# Controller_Sheet.net
KiCad netlist of a schematic drawn in Altium Designer
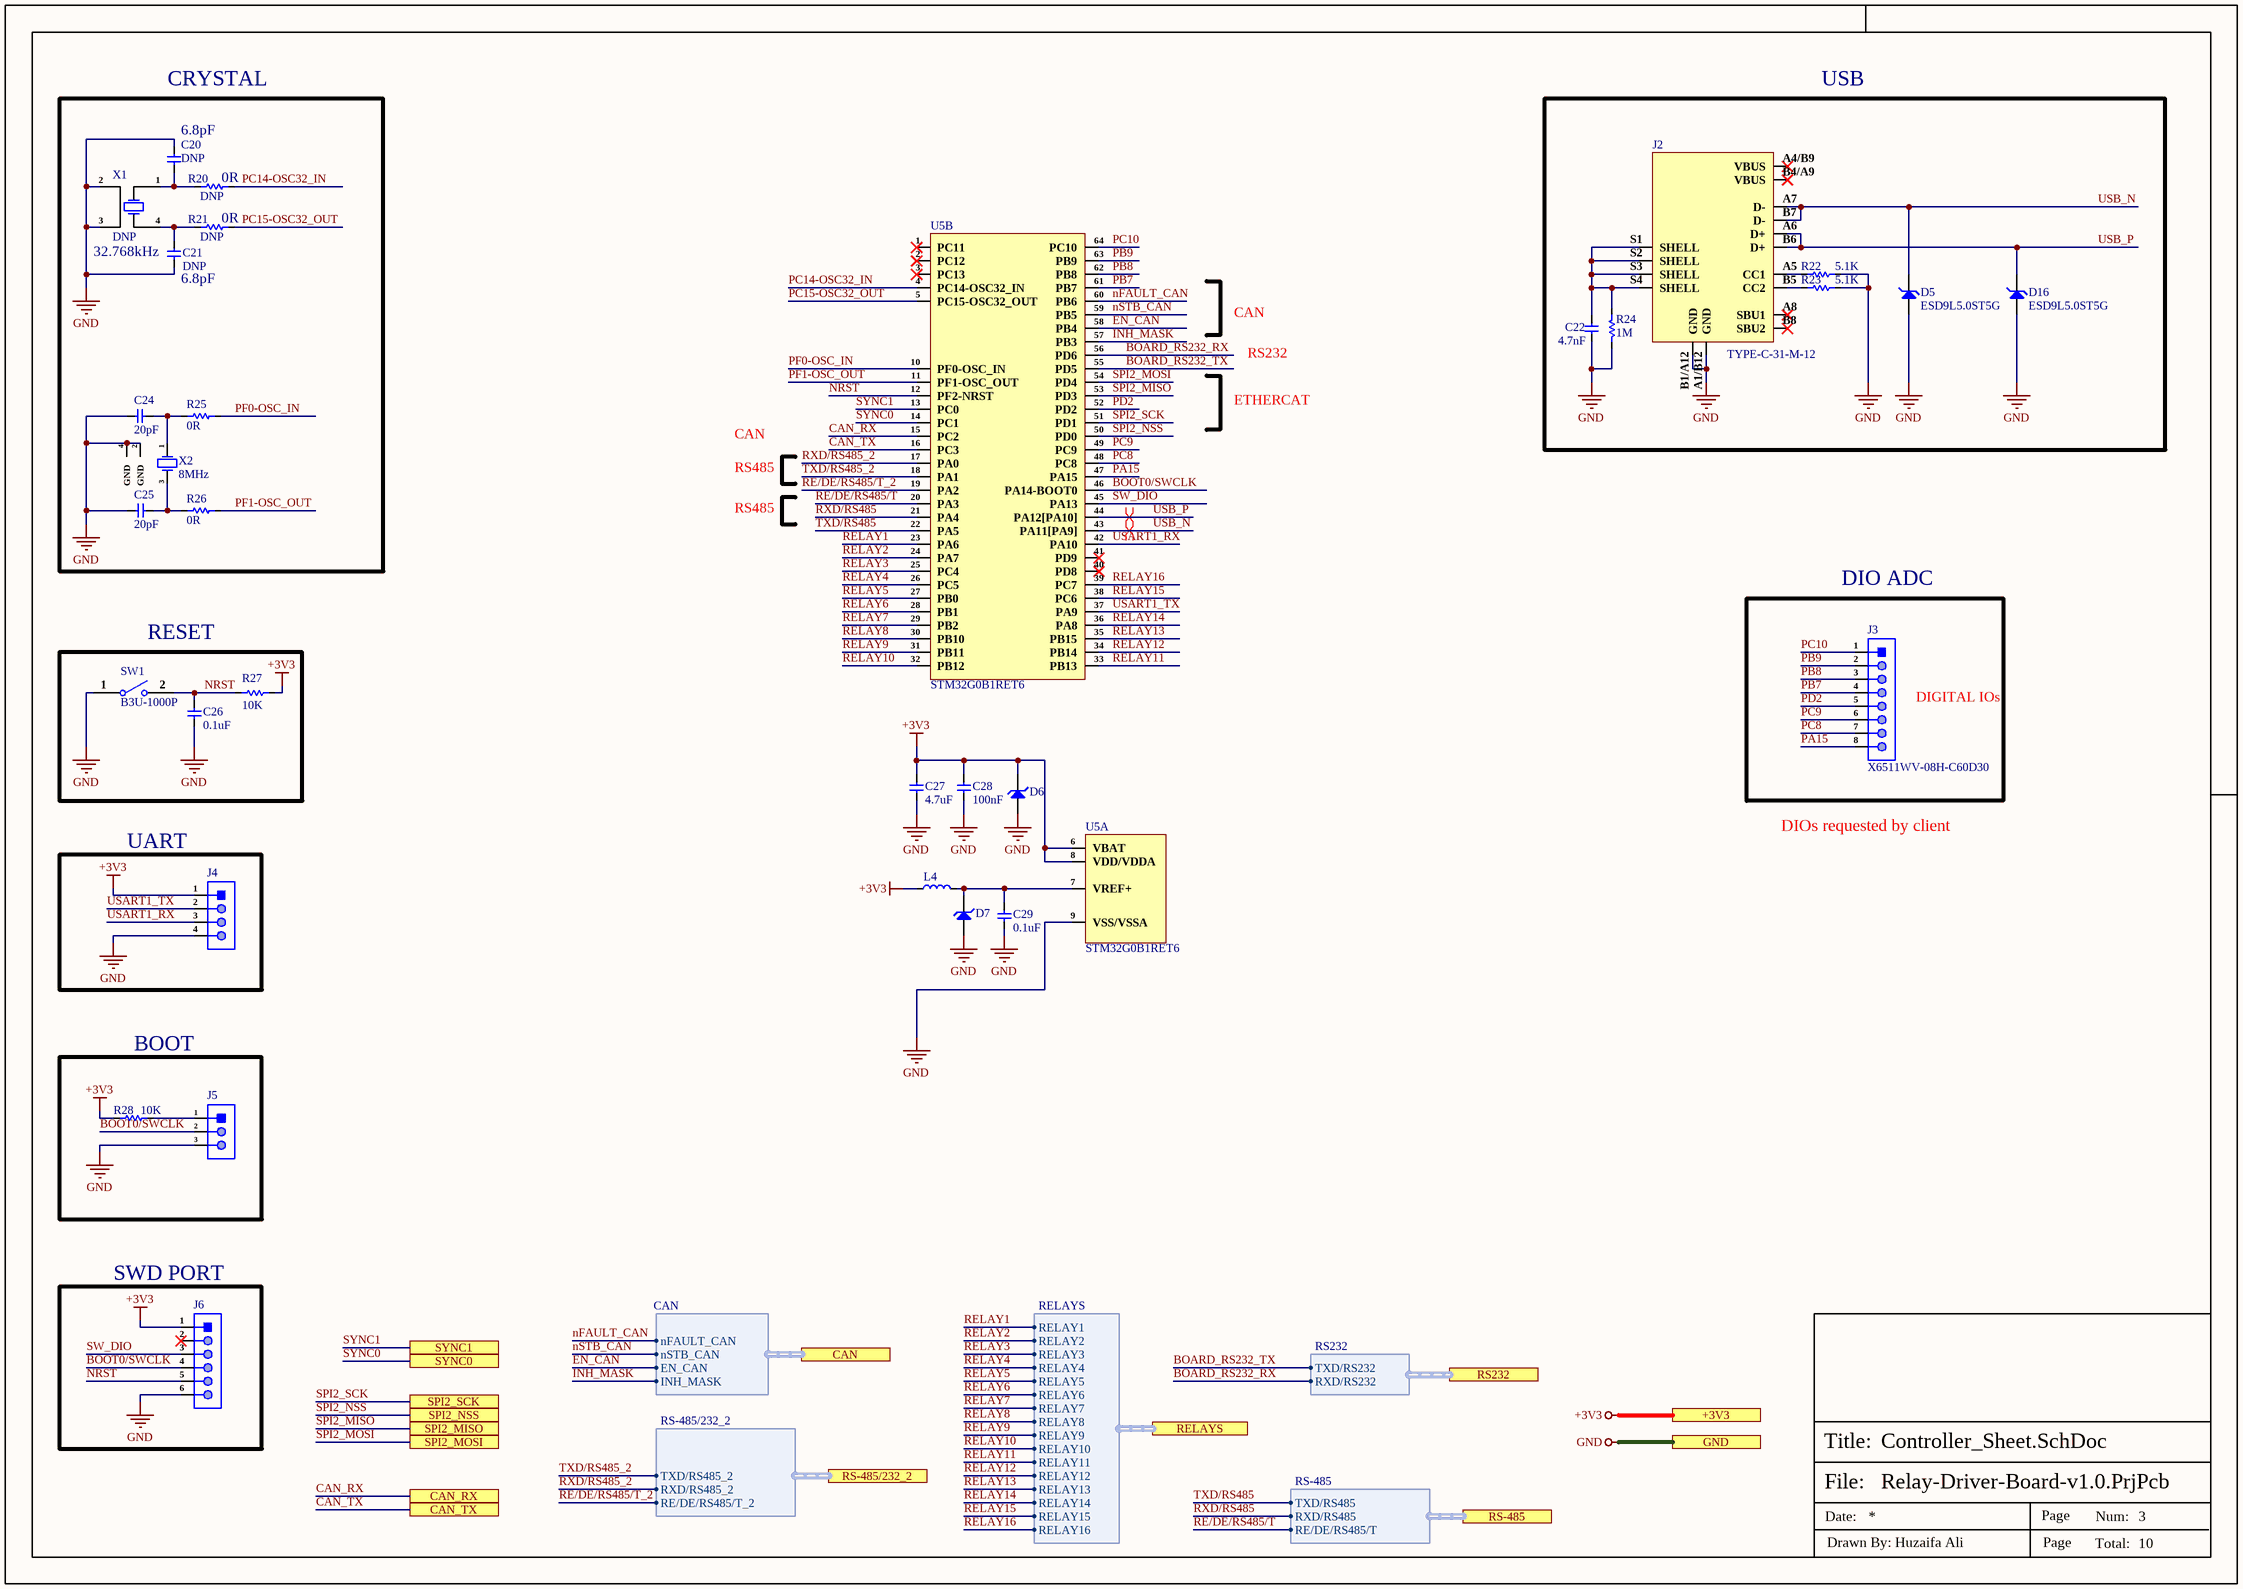
[diagram p0: Controller_Sheet.SchDoc]

(export (version "E")
  (design (tool "Eeschema 10.0.6"))
  (components
    (comp (ref "C20")
      (value "DNP")
      (footprint "Cap-0402")
      (description "CAP CER 6.8PF 50V C0G/NPO 0402")
      (fields
        (field (name "MANUFACTURER") "Yageo")
        (field (name "MANUFACTURER PART NUMBER") "CC0402CRNPO9BN6R8")
      )
      (libsource (lib "eSpark Libraries") (part "CC0402CRNPO9BN6R8"))
    )
    (comp (ref "C21")
      (value "DNP")
      (footprint "Cap-0402")
      (description "CAP CER 6.8PF 50V C0G/NPO 0402")
      (fields
        (field (name "MANUFACTURER") "Yageo")
        (field (name "MANUFACTURER PART NUMBER") "CC0402CRNPO9BN6R8")
      )
      (libsource (lib "eSpark Libraries") (part "CC0402CRNPO9BN6R8"))
    )
    (comp (ref "C22")
      (value "4.7nF")
      (footprint "Cap-0603")
      (description "CAP CER 4700PF 50V C0G/NPO 0603")
      (fields
        (field (name "MANUFACTURER") "Yageo")
        (field (name "MANUFACTURER PART NUMBER") "CC0603JRNPO9BN472")
      )
      (libsource (lib "eSpark_centralized_Library(2022)") (part "CC0603JRNPO9BN472"))
    )
    (comp (ref "C24")
      (value "20pF")
      (footprint "Cap-0402")
      (description "CAP CER 20PF 50V C0G/NPO 0402")
      (fields (field (name "LCSC PART NUMBER") "C107000") (field (name "MANUFACTURER") "Yageo"))
      (libsource (lib "eSpark Libraries") (part "CC0402JRNPO9BN200"))
    )
    (comp (ref "C25")
      (value "20pF")
      (footprint "Cap-0402")
      (description "CAP CER 20PF 50V C0G/NPO 0402")
      (fields (field (name "LCSC PART NUMBER") "C107000") (field (name "MANUFACTURER") "Yageo"))
      (libsource (lib "eSpark Libraries") (part "CC0402JRNPO9BN200"))
    )
    (comp (ref "C26")
      (value "0.1uF")
      (footprint "Cap-0402")
      (description "CAP CER 0.1UF 16V X7R 0402")
      (fields
        (field (name "MANUFACTURER") "Yageo")
        (field (name "MANUFACTURER PART NUMBER") "CC0402JRX7R7BB104")
      )
      (libsource (lib "eSpark Libraries") (part "CC0402JRX7R7BB104"))
    )
    (comp (ref "C27")
      (value "4.7uF")
      (footprint "Cap-0402")
      (description "CAP CER 4.7UF 10V X5R 0402")
      (fields
        (field (name "MANUFACTURER") "Yageo")
        (field (name "MANUFACTURER PART NUMBER") "CC0402KRX5R6BB475")
      )
      (libsource (lib "eSpark Libraries") (part "CC0402KRX5R6BB475"))
    )
    (comp (ref "C28")
      (value "100nF")
      (footprint "cap-0402")
      (description "CAP CER 0.1UF 50V X7R 0402")
      (fields
        (field (name "MANUFACTURER") "TDK")
        (field (name "MANUFACTURER PART NUMBER") "C1005X7R1H104KT000F")
      )
      (libsource (lib "eSpark Libraries") (part "C1005X7R1H104KT000F"))
    )
    (comp (ref "C29")
      (value "0.1uF")
      (footprint "Cap-0402")
      (description "CAP CER 0.1UF 16V X7R 0402")
      (fields
        (field (name "MANUFACTURER") "Yageo")
        (field (name "MANUFACTURER PART NUMBER") "CC0402JRX7R7BB104")
      )
      (libsource (lib "eSpark Libraries") (part "CC0402JRX7R7BB104"))
    )
    (comp (ref "D5")
      (value "ESD9L5.0ST5G")
      (footprint "SOD-923.")
      (description "TVS DIODE 5V 9.8V SOD923")
      (fields (field (name "MANUFACTURER") "ON Semiconductor") (field (name "LCSC PART NUMBER") "C82326"))
      (libsource (lib "eSpark Libraries") (part "ESD9L5.0ST5G"))
    )
    (comp (ref "D6")
      (value "AZ3003-01G")
      (footprint "SOD-123")
      (description "TVS SURGE PROTECTOR 1-CH 3.3V")
      (fields (field (name "MANUFACTURER") "Amazing"))
      (libsource (lib "eSpark Libraries") (part "AZ3003-01G"))
    )
    (comp (ref "D7")
      (value "AZ3003-01G")
      (footprint "SOD-123")
      (description "TVS SURGE PROTECTOR 1-CH 3.3V")
      (fields (field (name "MANUFACTURER") "Amazing"))
      (libsource (lib "eSpark Libraries") (part "AZ3003-01G"))
    )
    (comp (ref "D16")
      (value "ESD9L5.0ST5G")
      (footprint "SOD-923.")
      (description "TVS DIODE 5V 9.8V SOD923")
      (fields (field (name "MANUFACTURER") "ON Semiconductor") (field (name "LCSC PART NUMBER") "C82326"))
      (libsource (lib "eSpark Libraries") (part "ESD9L5.0ST5G"))
    )
    (comp (ref "J2")
      (value "TYPE-C-31-M-12")
      (footprint "TYPE-C-31-M-12_")
      (description "5A 1 16P Female Type-C SMD USB Connectors ROHS")
      (fields
        (field (name "MANUFACTURER") "Korean Hroparts Elec")
        (field (name "LCSC PART NUMBER") "C165948")
      )
      (libsource (lib "eSpark Libraries") (part "TYPE-C-31-M-12"))
    )
    (comp (ref "J3")
      (value "X6511WV-08H-C60D30")
      (footprint "HDR 1x8 TH male")
      (fields (field (name "MANUFACTURER") "XKB") (field (name "LCSC PART NUMBER") "C706880"))
      (libsource (lib "eSpark Libraries") (part "X6511WV-08H-C60D30"))
    )
    (comp (ref "J4")
      (value "X6511WV-04H-C60D30")
      (footprint "HDR1X4_")
      (fields (field (name "MANUFACTURER") "XKB") (field (name "LCSC PART NUMBER") "C706876"))
      (libsource (lib "eSpark Libraries") (part "X6511WV-04H-C60D30"))
    )
    (comp (ref "J5")
      (value "68000-103HLF")
      (footprint "HDR1X3_")
      (description "CONN HEADER VERT 3POS 2.54MM")
      (fields (field (name "LCSC PART NUMBER") "C168677"))
      (libsource (lib "eSpark Libraries") (part "68000-103HLF"))
    )
    (comp (ref "J6")
      (value "X6511WV-06H-C60D30")
      (footprint "HDR1X6_")
      (fields (field (name "MANUFACTURER") "XKB") (field (name "LCSC PART NUMBER") "C706878"))
      (libsource (lib "eSpark Libraries") (part "X6511WV-06H-C60D30"))
    )
    (comp (ref "L4")
      (value "BLM15AG601SN1D")
      (footprint "IND-0402")
      (description "FERRITE BEAD 600 OHM 0402 1LN")
      (fields (field (name "MANUFACTURER") "Murata") (field (name "TOLERANCE") "25%"))
      (libsource (lib "eSpark Libraries") (part "BLM15AG601SN1D"))
    )
    (comp (ref "R20")
      (value "DNP")
      (footprint "Res-0603")
      (description "RES 0 OHM JUMPER 1/10W 0603")
      (fields
        (field (name "MANUFACTURER") "Yageo")
        (field (name "MANUFACTURER PART NUMBER") "RC0603JR-070RL")
      )
      (libsource (lib "eSpark Libraries") (part "RC0603JR-070RL"))
    )
    (comp (ref "R21")
      (value "DNP")
      (footprint "Res-0603")
      (description "RES 0 OHM JUMPER 1/10W 0603")
      (fields
        (field (name "MANUFACTURER") "Yageo")
        (field (name "MANUFACTURER PART NUMBER") "RC0603JR-070RL")
      )
      (libsource (lib "eSpark Libraries") (part "RC0603JR-070RL"))
    )
    (comp (ref "R22")
      (value "5.1K")
      (footprint "Res-0402")
      (description "RES 5.1K OHM 1% 1/16W 0402")
      (fields
        (field (name "MANUFACTURER") "Yageo")
        (field (name "MANUFACTURER PART NUMBER") "RC0402FR-075K1L")
      )
      (libsource (lib "eSpark Libraries") (part "RC0402FR-075K1L"))
    )
    (comp (ref "R23")
      (value "5.1K")
      (footprint "Res-0402")
      (description "RES 5.1K OHM 1% 1/16W 0402")
      (fields
        (field (name "MANUFACTURER") "Yageo")
        (field (name "MANUFACTURER PART NUMBER") "RC0402FR-075K1L")
      )
      (libsource (lib "eSpark Libraries") (part "RC0402FR-075K1L"))
    )
    (comp (ref "R24")
      (value "1M")
      (footprint "Res-0402")
      (description "RES SMD 1M OHM 5% 1/16W 0402")
      (fields
        (field (name "MANUFACTURER") "Yageo")
        (field (name "MANUFACTURER PART NUMBER") "AF0402JR-071ML")
      )
      (libsource (lib "eSpark_centralized_Library(2022)") (part "AF0402JR-071ML"))
    )
    (comp (ref "R25")
      (value "0R")
      (footprint "Res-0603")
      (description "RES 0 OHM JUMPER 1/10W 0603")
      (fields
        (field (name "MANUFACTURER") "Yageo")
        (field (name "MANUFACTURER PART NUMBER") "RC0603JR-070RL")
      )
      (libsource (lib "eSpark Libraries") (part "RC0603JR-070RL"))
    )
    (comp (ref "R26")
      (value "0R")
      (footprint "Res-0603")
      (description "RES 0 OHM JUMPER 1/10W 0603")
      (fields
        (field (name "MANUFACTURER") "Yageo")
        (field (name "MANUFACTURER PART NUMBER") "RC0603JR-070RL")
      )
      (libsource (lib "eSpark Libraries") (part "RC0603JR-070RL"))
    )
    (comp (ref "R27")
      (value "10K")
      (footprint "Res-0402")
      (description "RES 10K OHM 1% 1/16W 0402")
      (fields
        (field (name "MANUFACTURER") "Yageo")
        (field (name "MANUFACTURER PART NUMBER") "RC0402FR-0710KL")
      )
      (libsource (lib "eSpark Libraries") (part "RC0402FR-0710KL"))
    )
    (comp (ref "R28")
      (value "10K")
      (footprint "Res-0402")
      (description "RES 10K OHM 1% 1/16W 0402")
      (fields
        (field (name "MANUFACTURER") "Yageo")
        (field (name "MANUFACTURER PART NUMBER") "RC0402FR-0710KL")
      )
      (libsource (lib "eSpark Libraries") (part "RC0402FR-0710KL"))
    )
    (comp (ref "SW1")
      (value "B3U-1000P")
      (footprint "B3U-1000P")
      (description "SWITCH TACTILE SPST-NO 0.05A 12V")
      (fields (field (name "MANUFACTURER") "Omron") (field (name "LCSC PART NUMBER") "C231329"))
      (libsource (lib "eSpark Libraries") (part "B3U-1000P"))
    )
    (comp (ref "U5")
      (value "STM32G0B1RET6")
      (footprint "LQFP-64(10x10)")
      (description "IC MCU 32BIT 512KB FLASH 64LQFP")
      (fields (field (name "MANUFACTURER") "STMicroelectronics") (field (name "LCSC PART NUMBER") "C2829307"))
      (libsource (lib "eSpark Libraries") (part "STM32G0B1RET6"))
    )
    (comp (ref "X1")
      (value "DNP")
      (footprint "MC-306")
      (description "32.768kHz 12.5pF ±20ppm MC-306 Crystals ROHS")
      (fields
        (field (name "MANUFACTURER") "Seiko Epson")
        (field (name "MANUFACTURER PART NUMBER") "MC-306 32.7680K-A0:ROHS")
      )
      (libsource (lib "eSpark Libraries") (part "MC-306 32.7680K-A0{colon}ROHS"))
    )
    (comp (ref "X2")
      (value "8MHz")
      (footprint "5TJ480000XYLBC_")
      (description "8MHz 18pF ±10ppm SMD5032-4P Crystals ROHS")
      (fields (field (name "MANUFACTURER") "JYJE") (field (name "MANUFACTURER PART NUMBER") "5TJ480000XYLBC"))
      (libsource (lib "eSpark Libraries") (part "5TJ480000XYLBC"))
    )
  )
  (nets
    (net (code "6") (name "+3V3") (class "Default")
      (node (ref "C27") (pin "2") (pinfunction "2_2") (pintype "passive"))
      (node (ref "C28") (pin "2") (pinfunction "2_2") (pintype "passive"))
      (node (ref "D6") (pin "2") (pinfunction "K_2") (pintype "passive"))
      (node (ref "J4") (pin "1") (pinfunction "1_1") (pintype "passive"))
      (node (ref "J6") (pin "1") (pinfunction "1_1") (pintype "passive"))
      (node (ref "L4") (pin "1") (pinfunction "1_1") (pintype "passive"))
      (node (ref "R27") (pin "2") (pinfunction "2_2") (pintype "passive"))
      (node (ref "R28") (pin "2") (pinfunction "2_2") (pintype "passive"))
      (node (ref "U5") (pin "6") (pinfunction "VBAT_6") (pintype "passive"))
      (node (ref "U5") (pin "8") (pinfunction "VDD/VDDA_8") (pintype "passive"))
    )
    (net (code "7") (name "/BOARD_RS232_RX") (class "Default")
      (node (ref "U5") (pin "56") (pinfunction "PD6_56") (pintype "passive"))
    )
    (net (code "8") (name "/BOARD_RS232_TX") (class "Default")
      (node (ref "U5") (pin "55") (pinfunction "PD5_55") (pintype "passive"))
    )
    (net (code "9") (name "/BOOT0{slash}SWCLK") (class "Default")
      (node (ref "J5") (pin "2") (pinfunction "2_2") (pintype "passive"))
      (node (ref "J6") (pin "4") (pinfunction "4_4") (pintype "passive"))
      (node (ref "U5") (pin "46") (pinfunction "PA14-BOOT0_46") (pintype "passive"))
    )
    (net (code "10") (name "/CAN_RX") (class "Default")
      (node (ref "U5") (pin "15") (pinfunction "PC2_15") (pintype "passive"))
    )
    (net (code "11") (name "/CAN_TX") (class "Default")
      (node (ref "U5") (pin "16") (pinfunction "PC3_16") (pintype "passive"))
    )
    (net (code "12") (name "/EN_CAN") (class "Default")
      (node (ref "U5") (pin "58") (pinfunction "PB4_58") (pintype "passive"))
    )
    (net (code "13") (name "/INH_MASK") (class "Default")
      (node (ref "U5") (pin "57") (pinfunction "PB3_57") (pintype "passive"))
    )
    (net (code "14") (name "/NRST") (class "Default")
      (node (ref "C26") (pin "2") (pinfunction "2_2") (pintype "passive"))
      (node (ref "J6") (pin "5") (pinfunction "5_5") (pintype "passive"))
      (node (ref "R27") (pin "1") (pinfunction "1_1") (pintype "passive"))
      (node (ref "SW1") (pin "2") (pinfunction "2_2") (pintype "passive"))
      (node (ref "U5") (pin "12") (pinfunction "PF2-NRST_12") (pintype "passive"))
    )
    (net (code "15") (name "/PA15") (class "Default")
      (node (ref "J3") (pin "8") (pinfunction "8_8") (pintype "passive"))
      (node (ref "U5") (pin "47") (pinfunction "PA15_47") (pintype "passive"))
    )
    (net (code "16") (name "/PB7") (class "Default")
      (node (ref "J3") (pin "4") (pinfunction "4_4") (pintype "passive"))
      (node (ref "U5") (pin "61") (pinfunction "PB7_61") (pintype "passive"))
    )
    (net (code "17") (name "/PB8") (class "Default")
      (node (ref "J3") (pin "3") (pinfunction "3_3") (pintype "passive"))
      (node (ref "U5") (pin "62") (pinfunction "PB8_62") (pintype "passive"))
    )
    (net (code "18") (name "/PB9") (class "Default")
      (node (ref "J3") (pin "2") (pinfunction "2_2") (pintype "passive"))
      (node (ref "U5") (pin "63") (pinfunction "PB9_63") (pintype "passive"))
    )
    (net (code "19") (name "/PC8") (class "Default")
      (node (ref "J3") (pin "7") (pinfunction "7_7") (pintype "passive"))
      (node (ref "U5") (pin "48") (pinfunction "PC8_48") (pintype "passive"))
    )
    (net (code "20") (name "/PC9") (class "Default")
      (node (ref "J3") (pin "6") (pinfunction "6_6") (pintype "passive"))
      (node (ref "U5") (pin "49") (pinfunction "PC9_49") (pintype "passive"))
    )
    (net (code "21") (name "/PC10") (class "Default")
      (node (ref "J3") (pin "1") (pinfunction "1_1") (pintype "passive"))
      (node (ref "U5") (pin "64") (pinfunction "PC10_64") (pintype "passive"))
    )
    (net (code "22") (name "/PC14-OSC32_IN") (class "Default")
      (node (ref "R20") (pin "2") (pinfunction "2_2") (pintype "passive"))
      (node (ref "U5") (pin "4") (pinfunction "PC14-OSC32_IN_4") (pintype "passive"))
    )
    (net (code "23") (name "/PC15-OSC32_OUT") (class "Default")
      (node (ref "R21") (pin "2") (pinfunction "2_2") (pintype "passive"))
      (node (ref "U5") (pin "5") (pinfunction "PC15-OSC32_OUT_5") (pintype "passive"))
    )
    (net (code "24") (name "/PD2") (class "Default")
      (node (ref "J3") (pin "5") (pinfunction "5_5") (pintype "passive"))
      (node (ref "U5") (pin "52") (pinfunction "PD2_52") (pintype "passive"))
    )
    (net (code "25") (name "/PF0-OSC_IN") (class "Default")
      (node (ref "R25") (pin "2") (pinfunction "2_2") (pintype "passive"))
      (node (ref "U5") (pin "10") (pinfunction "PF0-OSC_IN_10") (pintype "passive"))
    )
    (net (code "26") (name "/PF1-OSC_OUT") (class "Default")
      (node (ref "R26") (pin "2") (pinfunction "2_2") (pintype "passive"))
      (node (ref "U5") (pin "11") (pinfunction "PF1-OSC_OUT_11") (pintype "passive"))
    )
    (net (code "27") (name "/RELAY1") (class "Default")
      (node (ref "U5") (pin "23") (pinfunction "PA6_23") (pintype "passive"))
    )
    (net (code "28") (name "/RELAY2") (class "Default")
      (node (ref "U5") (pin "24") (pinfunction "PA7_24") (pintype "passive"))
    )
    (net (code "29") (name "/RELAY3") (class "Default")
      (node (ref "U5") (pin "25") (pinfunction "PC4_25") (pintype "passive"))
    )
    (net (code "30") (name "/RELAY4") (class "Default")
      (node (ref "U5") (pin "26") (pinfunction "PC5_26") (pintype "passive"))
    )
    (net (code "31") (name "/RELAY5") (class "Default")
      (node (ref "U5") (pin "27") (pinfunction "PB0_27") (pintype "passive"))
    )
    (net (code "32") (name "/RELAY6") (class "Default")
      (node (ref "U5") (pin "28") (pinfunction "PB1_28") (pintype "passive"))
    )
    (net (code "33") (name "/RELAY7") (class "Default")
      (node (ref "U5") (pin "29") (pinfunction "PB2_29") (pintype "passive"))
    )
    (net (code "34") (name "/RELAY8") (class "Default")
      (node (ref "U5") (pin "30") (pinfunction "PB10_30") (pintype "passive"))
    )
    (net (code "35") (name "/RELAY9") (class "Default")
      (node (ref "U5") (pin "31") (pinfunction "PB11_31") (pintype "passive"))
    )
    (net (code "36") (name "/RELAY10") (class "Default")
      (node (ref "U5") (pin "32") (pinfunction "PB12_32") (pintype "passive"))
    )
    (net (code "37") (name "/RELAY11") (class "Default")
      (node (ref "U5") (pin "33") (pinfunction "PB13_33") (pintype "passive"))
    )
    (net (code "38") (name "/RELAY12") (class "Default")
      (node (ref "U5") (pin "34") (pinfunction "PB14_34") (pintype "passive"))
    )
    (net (code "39") (name "/RELAY13") (class "Default")
      (node (ref "U5") (pin "35") (pinfunction "PB15_35") (pintype "passive"))
    )
    (net (code "40") (name "/RELAY14") (class "Default")
      (node (ref "U5") (pin "36") (pinfunction "PA8_36") (pintype "passive"))
    )
    (net (code "41") (name "/RELAY15") (class "Default")
      (node (ref "U5") (pin "38") (pinfunction "PC6_38") (pintype "passive"))
    )
    (net (code "42") (name "/RELAY16") (class "Default")
      (node (ref "U5") (pin "39") (pinfunction "PC7_39") (pintype "passive"))
    )
    (net (code "43") (name "/RE{slash}DE{slash}RS485{slash}T") (class "Default")
      (node (ref "U5") (pin "20") (pinfunction "PA3_20") (pintype "passive"))
    )
    (net (code "44") (name "/RE{slash}DE{slash}RS485{slash}T_2") (class "Default")
      (node (ref "U5") (pin "19") (pinfunction "PA2_19") (pintype "passive"))
    )
    (net (code "45") (name "/RXD{slash}RS485") (class "Default")
      (node (ref "U5") (pin "21") (pinfunction "PA4_21") (pintype "passive"))
    )
    (net (code "46") (name "/RXD{slash}RS485_2") (class "Default")
      (node (ref "U5") (pin "17") (pinfunction "PA0_17") (pintype "passive"))
    )
    (net (code "47") (name "/SPI2_MISO") (class "Default")
      (node (ref "U5") (pin "53") (pinfunction "PD3_53") (pintype "passive"))
    )
    (net (code "48") (name "/SPI2_MOSI") (class "Default")
      (node (ref "U5") (pin "54") (pinfunction "PD4_54") (pintype "passive"))
    )
    (net (code "49") (name "/SPI2_NSS") (class "Default")
      (node (ref "U5") (pin "50") (pinfunction "PD0_50") (pintype "passive"))
    )
    (net (code "50") (name "/SPI2_SCK") (class "Default")
      (node (ref "U5") (pin "51") (pinfunction "PD1_51") (pintype "passive"))
    )
    (net (code "51") (name "/SW_DIO") (class "Default")
      (node (ref "J6") (pin "3") (pinfunction "3_3") (pintype "passive"))
      (node (ref "U5") (pin "45") (pinfunction "PA13_45") (pintype "passive"))
    )
    (net (code "52") (name "/SYNC0") (class "Default")
      (node (ref "U5") (pin "14") (pinfunction "PC1_14") (pintype "passive"))
    )
    (net (code "53") (name "/SYNC1") (class "Default")
      (node (ref "U5") (pin "13") (pinfunction "PC0_13") (pintype "passive"))
    )
    (net (code "54") (name "/TXD{slash}RS485") (class "Default")
      (node (ref "U5") (pin "22") (pinfunction "PA5_22") (pintype "passive"))
    )
    (net (code "55") (name "/TXD{slash}RS485_2") (class "Default")
      (node (ref "U5") (pin "18") (pinfunction "PA1_18") (pintype "passive"))
    )
    (net (code "56") (name "/USART1_RX") (class "Default")
      (node (ref "J4") (pin "3") (pinfunction "3_3") (pintype "passive"))
      (node (ref "U5") (pin "42") (pinfunction "PA10_42") (pintype "passive"))
    )
    (net (code "57") (name "/USART1_TX") (class "Default")
      (node (ref "J4") (pin "2") (pinfunction "2_2") (pintype "passive"))
      (node (ref "U5") (pin "37") (pinfunction "PA9_37") (pintype "passive"))
    )
    (net (code "58") (name "/USB_N") (class "Default")
      (node (ref "D5") (pin "1") (pinfunction "K_1") (pintype "passive"))
      (node (ref "J2") (pin "A7") (pinfunction "D-_A7") (pintype "passive"))
      (node (ref "J2") (pin "B7") (pinfunction "D-_B7") (pintype "passive"))
      (node (ref "U5") (pin "43") (pinfunction "PA11[PA9]_43") (pintype "passive"))
    )
    (net (code "59") (name "/USB_P") (class "Default")
      (node (ref "D16") (pin "1") (pinfunction "K_1") (pintype "passive"))
      (node (ref "J2") (pin "A6") (pinfunction "D+_A6") (pintype "passive"))
      (node (ref "J2") (pin "B6") (pinfunction "D+_B6") (pintype "passive"))
      (node (ref "U5") (pin "44") (pinfunction "PA12[PA10]_44") (pintype "passive"))
    )
    (net (code "60") (name "/nFAULT_CAN") (class "Default")
      (node (ref "U5") (pin "60") (pinfunction "PB6_60") (pintype "passive"))
    )
    (net (code "61") (name "/nSTB_CAN") (class "Default")
      (node (ref "U5") (pin "59") (pinfunction "PB5_59") (pintype "passive"))
    )
    (net (code "67") (name "GND") (class "Default")
      (node (ref "C20") (pin "1") (pinfunction "1_1") (pintype "passive"))
      (node (ref "C21") (pin "2") (pinfunction "2_2") (pintype "passive"))
      (node (ref "C22") (pin "1") (pinfunction "1_1") (pintype "passive"))
      (node (ref "C24") (pin "1") (pinfunction "1_1") (pintype "passive"))
      (node (ref "C25") (pin "2") (pinfunction "2_2") (pintype "passive"))
      (node (ref "C26") (pin "1") (pinfunction "1_1") (pintype "passive"))
      (node (ref "C27") (pin "1") (pinfunction "1_1") (pintype "passive"))
      (node (ref "C28") (pin "1") (pinfunction "1_1") (pintype "passive"))
      (node (ref "C29") (pin "1") (pinfunction "1_1") (pintype "passive"))
      (node (ref "D16") (pin "2") (pinfunction "A_2") (pintype "passive"))
      (node (ref "D5") (pin "2") (pinfunction "A_2") (pintype "passive"))
      (node (ref "D6") (pin "1") (pinfunction "A_1") (pintype "passive"))
      (node (ref "D7") (pin "1") (pinfunction "A_1") (pintype "passive"))
      (node (ref "J2") (pin "A1/B12") (pinfunction "GND_A1/B12") (pintype "power_in"))
      (node (ref "J2") (pin "B1/A12") (pinfunction "GND_B1/A12") (pintype "power_in"))
      (node (ref "J4") (pin "4") (pinfunction "4_4") (pintype "passive"))
      (node (ref "J5") (pin "3") (pinfunction "3_3") (pintype "passive"))
      (node (ref "J6") (pin "6") (pinfunction "6_6") (pintype "passive"))
      (node (ref "R22") (pin "2") (pinfunction "2_2") (pintype "passive"))
      (node (ref "R23") (pin "2") (pinfunction "2_2") (pintype "passive"))
      (node (ref "R24") (pin "2") (pinfunction "2_2") (pintype "passive"))
      (node (ref "SW1") (pin "1") (pinfunction "1_1") (pintype "passive"))
      (node (ref "U5") (pin "9") (pinfunction "VSS/VSSA_9") (pintype "passive"))
      (node (ref "X1") (pin "2") (pinfunction "2_2") (pintype "passive"))
      (node (ref "X1") (pin "3") (pinfunction "3_3") (pintype "passive"))
      (node (ref "X2") (pin "2") (pinfunction "GND_2") (pintype "passive"))
      (node (ref "X2") (pin "4") (pinfunction "GND_4") (pintype "passive"))
    )
    (net (code "68") (name "Net-(C22-Pad2)") (class "Default")
      (node (ref "C22") (pin "2") (pinfunction "2_2") (pintype "passive"))
      (node (ref "J2") (pin "S1") (pinfunction "SHELL_S1") (pintype "passive"))
      (node (ref "J2") (pin "S2") (pinfunction "SHELL_S2") (pintype "passive"))
      (node (ref "J2") (pin "S3") (pinfunction "SHELL_S3") (pintype "passive"))
      (node (ref "J2") (pin "S4") (pinfunction "SHELL_S4") (pintype "passive"))
      (node (ref "R24") (pin "1") (pinfunction "1_1") (pintype "passive"))
    )
    (net (code "69") (name "Net-(D7-K)") (class "Default")
      (node (ref "C29") (pin "2") (pinfunction "2_2") (pintype "passive"))
      (node (ref "D7") (pin "2") (pinfunction "K_2") (pintype "passive"))
      (node (ref "L4") (pin "2") (pinfunction "2_2") (pintype "passive"))
      (node (ref "U5") (pin "7") (pinfunction "VREF+_7") (pintype "passive"))
    )
    (net (code "70") (name "Net-(J2-CC1)") (class "Default")
      (node (ref "J2") (pin "A5") (pinfunction "CC1_A5") (pintype "passive"))
      (node (ref "R22") (pin "1") (pinfunction "1_1") (pintype "passive"))
    )
    (net (code "71") (name "Net-(J2-CC2)") (class "Default")
      (node (ref "J2") (pin "B5") (pinfunction "CC2_B5") (pintype "passive"))
      (node (ref "R23") (pin "1") (pinfunction "1_1") (pintype "passive"))
    )
    (net (code "72") (name "Net-(J5-Pad1)") (class "Default")
      (node (ref "J5") (pin "1") (pinfunction "1_1") (pintype "passive"))
      (node (ref "R28") (pin "1") (pinfunction "1_1") (pintype "passive"))
    )
    (net (code "73") (name "Net-(X1-OSC1)") (class "Default")
      (node (ref "C20") (pin "2") (pinfunction "2_2") (pintype "passive"))
      (node (ref "R20") (pin "1") (pinfunction "1_1") (pintype "passive"))
      (node (ref "X1") (pin "1") (pinfunction "OSC1_1") (pintype "passive"))
    )
    (net (code "74") (name "Net-(X1-OSC2)") (class "Default")
      (node (ref "C21") (pin "1") (pinfunction "1_1") (pintype "passive"))
      (node (ref "R21") (pin "1") (pinfunction "1_1") (pintype "passive"))
      (node (ref "X1") (pin "4") (pinfunction "OSC2_4") (pintype "passive"))
    )
    (net (code "75") (name "Net-(X2-OSC1)") (class "Default")
      (node (ref "C24") (pin "2") (pinfunction "2_2") (pintype "passive"))
      (node (ref "R25") (pin "1") (pinfunction "1_1") (pintype "passive"))
      (node (ref "X2") (pin "1") (pinfunction "OSC1_1") (pintype "passive"))
    )
    (net (code "76") (name "Net-(X2-OSC2)") (class "Default")
      (node (ref "C25") (pin "1") (pinfunction "1_1") (pintype "passive"))
      (node (ref "R26") (pin "1") (pinfunction "1_1") (pintype "passive"))
      (node (ref "X2") (pin "3") (pinfunction "OSC2_3") (pintype "passive"))
    )
    (net (code "77") (name "unconnected-(J2-SBU1-PadA8)") (class "Default")
      (node (ref "J2") (pin "A8") (pinfunction "SBU1_A8") (pintype "passive+no_connect"))
    )
    (net (code "78") (name "unconnected-(J2-SBU2-PadB8)") (class "Default")
      (node (ref "J2") (pin "B8") (pinfunction "SBU2_B8") (pintype "passive+no_connect"))
    )
    (net (code "79") (name "unconnected-(J2-VBUS-PadA4{slash}B9)") (class "Default")
      (node (ref "J2") (pin "A4/B9") (pinfunction "VBUS_A4/B9") (pintype "power_in+no_connect"))
    )
    (net (code "80") (name "unconnected-(J2-VBUS-PadB4{slash}A9)") (class "Default")
      (node (ref "J2") (pin "B4/A9") (pinfunction "VBUS_B4/A9") (pintype "power_in+no_connect"))
    )
    (net (code "81") (name "unconnected-(J6-Pad2)") (class "Default")
      (node (ref "J6") (pin "2") (pinfunction "2_2") (pintype "passive+no_connect"))
    )
    (net (code "82") (name "unconnected-(U5B-PC11-Pad1)") (class "Default")
      (node (ref "U5") (pin "1") (pinfunction "PC11_1") (pintype "passive+no_connect"))
    )
    (net (code "83") (name "unconnected-(U5B-PC12-Pad2)") (class "Default")
      (node (ref "U5") (pin "2") (pinfunction "PC12_2") (pintype "passive+no_connect"))
    )
    (net (code "84") (name "unconnected-(U5B-PC13-Pad3)") (class "Default")
      (node (ref "U5") (pin "3") (pinfunction "PC13_3") (pintype "passive+no_connect"))
    )
    (net (code "85") (name "unconnected-(U5B-PD8-Pad40)") (class "Default")
      (node (ref "U5") (pin "40") (pinfunction "PD8_40") (pintype "passive+no_connect"))
    )
    (net (code "86") (name "unconnected-(U5B-PD9-Pad41)") (class "Default")
      (node (ref "U5") (pin "41") (pinfunction "PD9_41") (pintype "passive+no_connect"))
    )
  )
)
